# bene2stmbl-smd.net
KiCad netlist of a schematic drawn in EAGLE
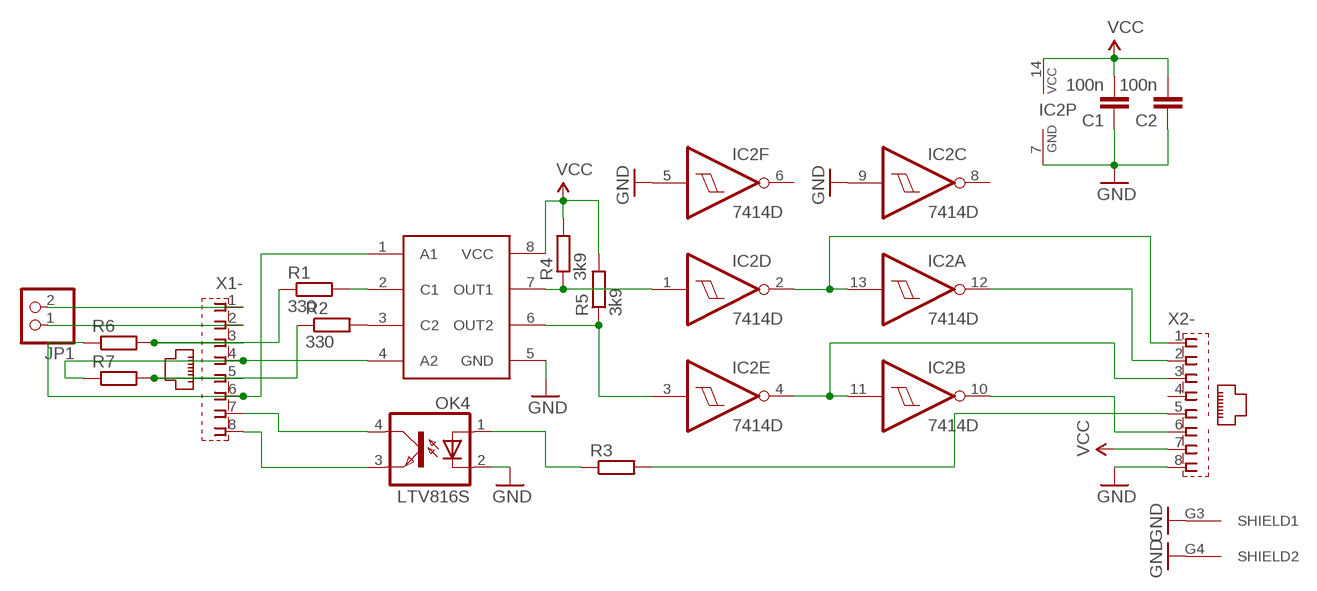
[diagram p0: schematic, sheet 1]

(export (version "E")
  (design (tool "Eeschema 10.0.6"))
  (components
    (comp (ref "C1")
      (value "100n")
      (footprint "eagle-import:C0603")
      (libsource (lib "eagle-import") (part "C-EUC0603"))
    )
    (comp (ref "C2")
      (value "100n")
      (footprint "eagle-import:C0603")
      (libsource (lib "eagle-import") (part "C-EUC0603"))
    )
    (comp (ref "IC2")
      (value "7414D")
      (footprint "eagle-import:SO14")
      (libsource (lib "eagle-import") (part "7414D"))
    )
    (comp (ref "JP1")
      (value "PINHD-1X2")
      (footprint "eagle-import:1X02")
      (libsource (lib "eagle-import") (part "PINHD-1X2"))
    )
    (comp (ref "OK4")
      (value "LTV816S")
      (footprint "eagle-import:SMD4")
      (libsource (lib "eagle-import") (part "LTV816S"))
    )
    (comp (ref "R1")
      (value "330")
      (footprint "eagle-import:R0603")
      (libsource (lib "eagle-import") (part "R-EU_R0603"))
    )
    (comp (ref "R2")
      (value "330")
      (footprint "eagle-import:R0603")
      (libsource (lib "eagle-import") (part "R-EU_R0603"))
    )
    (comp (ref "R3")
      (value "R-EU_R0603")
      (footprint "eagle-import:R0603")
      (libsource (lib "eagle-import") (part "R-EU_R0603"))
    )
    (comp (ref "R4")
      (value "3k9")
      (footprint "eagle-import:R0603")
      (libsource (lib "eagle-import") (part "R-EU_R0603"))
    )
    (comp (ref "R5")
      (value "3k9")
      (footprint "eagle-import:R0603")
      (libsource (lib "eagle-import") (part "R-EU_R0603"))
    )
    (comp (ref "R6")
      (value "R-EU_R0603")
      (footprint "eagle-import:R0603")
      (libsource (lib "eagle-import") (part "R-EU_R0603"))
    )
    (comp (ref "R7")
      (value "R-EU_R0603")
      (footprint "eagle-import:R0603")
      (libsource (lib "eagle-import") (part "R-EU_R0603"))
    )
    (comp (ref "U$1")
      (value "HCPL-053L-SMD")
      (footprint "eagle-import:SO08")
      (libsource (lib "eagle-import") (part "HCPL-053L-SMD"))
    )
    (comp (ref "X1")
      (value "RJ45")
      (footprint "eagle-import:RJ45")
      (libsource (lib "eagle-import") (part "RJ45"))
    )
    (comp (ref "X2")
      (value "RJ45")
      (footprint "eagle-import:RJ45")
      (libsource (lib "eagle-import") (part "RJ45"))
    )
  )
  (nets
    (net (code "1") (name "GND") (class "Default")
      (node (ref "C1") (pin "1") (pinfunction "1_1") (pintype "passive"))
      (node (ref "C2") (pin "1") (pinfunction "1_1") (pintype "passive"))
      (node (ref "IC2") (pin "5") (pinfunction "I_5") (pintype "input"))
      (node (ref "IC2") (pin "7") (pinfunction "GND_7") (pintype "power_in"))
      (node (ref "IC2") (pin "9") (pinfunction "I_9") (pintype "input"))
      (node (ref "OK4") (pin "2") (pinfunction "C_2") (pintype "passive"))
      (node (ref "U$1") (pin "5") (pinfunction "GND_5") (pintype "bidirectional"))
      (node (ref "X2") (pin "8") (pinfunction "8_8") (pintype "passive"))
      (node (ref "X2") (pin "G3") (pinfunction "SHIELD1_G3") (pintype "bidirectional"))
      (node (ref "X2") (pin "G4") (pinfunction "SHIELD2_G4") (pintype "bidirectional"))
    )
    (net (code "2") (name "Net-(IC2A-I)") (class "Default")
      (node (ref "IC2") (pin "13") (pinfunction "I_13") (pintype "input"))
      (node (ref "IC2") (pin "2") (pinfunction "O_2") (pintype "output"))
      (node (ref "X2") (pin "1") (pinfunction "1_1") (pintype "passive"))
    )
    (net (code "3") (name "Net-(IC2A-O)") (class "Default")
      (node (ref "IC2") (pin "12") (pinfunction "O_12") (pintype "output"))
      (node (ref "X2") (pin "2") (pinfunction "2_2") (pintype "passive"))
    )
    (net (code "4") (name "Net-(IC2B-I)") (class "Default")
      (node (ref "IC2") (pin "11") (pinfunction "I_11") (pintype "input"))
      (node (ref "IC2") (pin "4") (pinfunction "O_4") (pintype "output"))
      (node (ref "X2") (pin "3") (pinfunction "3_3") (pintype "passive"))
    )
    (net (code "5") (name "Net-(IC2B-O)") (class "Default")
      (node (ref "IC2") (pin "10") (pinfunction "O_10") (pintype "output"))
      (node (ref "X2") (pin "6") (pinfunction "6_6") (pintype "passive"))
    )
    (net (code "6") (name "Net-(IC2D-I)") (class "Default")
      (node (ref "IC2") (pin "1") (pinfunction "I_1") (pintype "input"))
      (node (ref "R4") (pin "1") (pinfunction "1_1") (pintype "passive"))
      (node (ref "U$1") (pin "7") (pinfunction "OUT1_7") (pintype "bidirectional"))
    )
    (net (code "7") (name "Net-(IC2E-I)") (class "Default")
      (node (ref "IC2") (pin "3") (pinfunction "I_3") (pintype "input"))
      (node (ref "R5") (pin "1") (pinfunction "1_1") (pintype "passive"))
      (node (ref "U$1") (pin "6") (pinfunction "OUT2_6") (pintype "bidirectional"))
    )
    (net (code "8") (name "Net-(JP1-Pad1)") (class "Default")
      (node (ref "JP1") (pin "1") (pinfunction "1_1") (pintype "passive"))
      (node (ref "X1") (pin "2") (pinfunction "2_2") (pintype "passive"))
    )
    (net (code "9") (name "Net-(JP1-Pad2)") (class "Default")
      (node (ref "JP1") (pin "2") (pinfunction "2_2") (pintype "passive"))
      (node (ref "X1") (pin "1") (pinfunction "1_1") (pintype "passive"))
    )
    (net (code "10") (name "Net-(OK4-A)") (class "Default")
      (node (ref "OK4") (pin "1") (pinfunction "A_1") (pintype "passive"))
      (node (ref "R3") (pin "1") (pinfunction "1_1") (pintype "passive"))
    )
    (net (code "11") (name "Net-(OK4-COL)") (class "Default")
      (node (ref "OK4") (pin "4") (pinfunction "COL_4") (pintype "passive"))
      (node (ref "X1") (pin "7") (pinfunction "7_7") (pintype "passive"))
    )
    (net (code "12") (name "Net-(OK4-EMIT)") (class "Default")
      (node (ref "OK4") (pin "3") (pinfunction "EMIT_3") (pintype "passive"))
      (node (ref "X1") (pin "8") (pinfunction "8_8") (pintype "passive"))
    )
    (net (code "13") (name "Net-(R1-Pad1)") (class "Default")
      (node (ref "R1") (pin "1") (pinfunction "1_1") (pintype "passive"))
      (node (ref "R6") (pin "2") (pinfunction "2_2") (pintype "passive"))
      (node (ref "X1") (pin "3") (pinfunction "3_3") (pintype "passive"))
    )
    (net (code "14") (name "Net-(R2-Pad1)") (class "Default")
      (node (ref "R2") (pin "1") (pinfunction "1_1") (pintype "passive"))
      (node (ref "R7") (pin "2") (pinfunction "2_2") (pintype "passive"))
      (node (ref "X1") (pin "5") (pinfunction "5_5") (pintype "passive"))
    )
    (net (code "15") (name "Net-(R3-Pad2)") (class "Default")
      (node (ref "R3") (pin "2") (pinfunction "2_2") (pintype "passive"))
      (node (ref "X2") (pin "5") (pinfunction "5_5") (pintype "passive"))
    )
    (net (code "16") (name "Net-(U$1-A1)") (class "Default")
      (node (ref "R6") (pin "1") (pinfunction "1_1") (pintype "passive"))
      (node (ref "U$1") (pin "1") (pinfunction "A1_1") (pintype "bidirectional"))
      (node (ref "X1") (pin "6") (pinfunction "6_6") (pintype "passive"))
    )
    (net (code "17") (name "Net-(U$1-A2)") (class "Default")
      (node (ref "R7") (pin "1") (pinfunction "1_1") (pintype "passive"))
      (node (ref "U$1") (pin "4") (pinfunction "A2_4") (pintype "bidirectional"))
      (node (ref "X1") (pin "4") (pinfunction "4_4") (pintype "passive"))
    )
    (net (code "18") (name "Net-(U$1-C1)") (class "Default")
      (node (ref "R1") (pin "2") (pinfunction "2_2") (pintype "passive"))
      (node (ref "U$1") (pin "2") (pinfunction "C1_2") (pintype "bidirectional"))
    )
    (net (code "19") (name "Net-(U$1-C2)") (class "Default")
      (node (ref "R2") (pin "2") (pinfunction "2_2") (pintype "passive"))
      (node (ref "U$1") (pin "3") (pinfunction "C2_3") (pintype "bidirectional"))
    )
    (net (code "20") (name "VCC") (class "Default")
      (node (ref "C1") (pin "2") (pinfunction "2_2") (pintype "passive"))
      (node (ref "C2") (pin "2") (pinfunction "2_2") (pintype "passive"))
      (node (ref "IC2") (pin "14") (pinfunction "VCC_14") (pintype "power_in"))
      (node (ref "R4") (pin "2") (pinfunction "2_2") (pintype "passive"))
      (node (ref "R5") (pin "2") (pinfunction "2_2") (pintype "passive"))
      (node (ref "U$1") (pin "8") (pinfunction "VCC_8") (pintype "bidirectional"))
      (node (ref "X2") (pin "7") (pinfunction "7_7") (pintype "passive"))
    )
    (net (code "21") (name "unconnected-(IC2C-O-Pad8)") (class "Default")
      (node (ref "IC2") (pin "8") (pinfunction "O_8") (pintype "output"))
    )
    (net (code "22") (name "unconnected-(IC2F-O-Pad6)") (class "Default")
      (node (ref "IC2") (pin "6") (pinfunction "O_6") (pintype "output"))
    )
    (net (code "23") (name "unconnected-(X2-Pad4)") (class "Default")
      (node (ref "X2") (pin "4") (pinfunction "4_4") (pintype "passive"))
    )
  )
)
